# Anchor_G431.net
KiCad netlist of a schematic drawn in Altium Designer
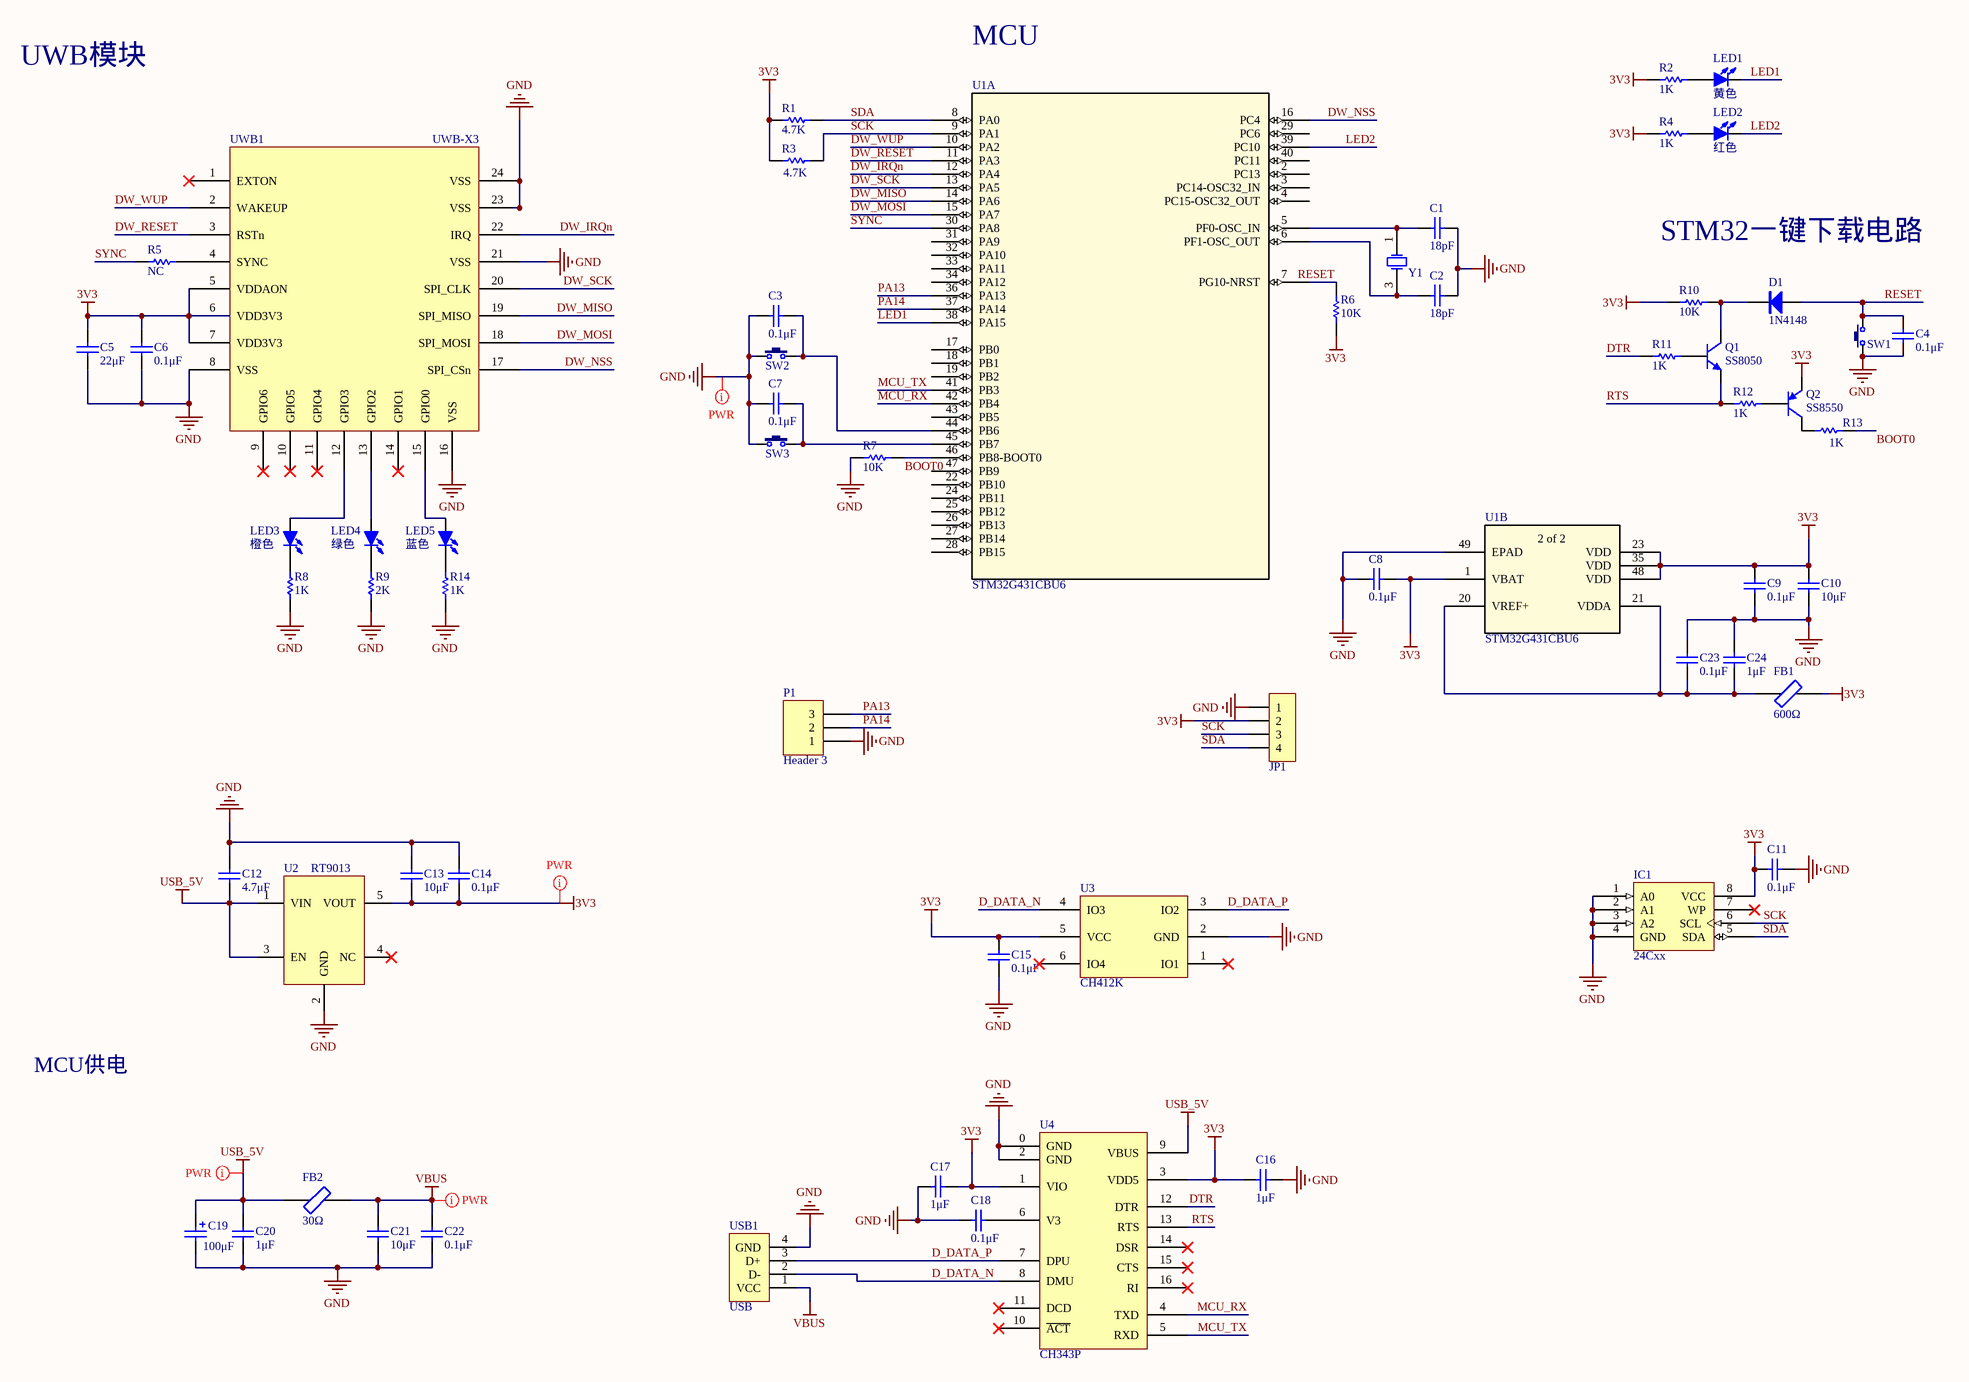
[diagram p0: Anchor_G431.SchDoc]

(export (version "E")
  (design (tool "Eeschema 10.0.6"))
  (components
    (comp (ref "C1")
      (value "18pF")
      (footprint "C 0603_L")
      (description "Capacitor")
      (fields (field (name "Comment") "Cap") (field (name "PUBLISHER") "Altium Limited"))
      (libsource (lib "Nixie") (part "Cap"))
    )
    (comp (ref "C2")
      (value "18pF")
      (footprint "C 0603_L")
      (description "Capacitor")
      (fields (field (name "Comment") "Cap") (field (name "PUBLISHER") "Altium Limited"))
      (libsource (lib "Nixie") (part "Cap"))
    )
    (comp (ref "C3")
      (value "0.1μF")
      (footprint "C 0603_L")
      (description "Capacitor")
      (fields (field (name "Comment") "Cap") (field (name "PUBLISHER") "Altium Limited"))
      (libsource (lib "Nixie") (part "Cap"))
    )
    (comp (ref "C4")
      (value "0.1μF")
      (footprint "C 0603_L")
      (description "Capacitor")
      (fields (field (name "Comment") "Cap") (field (name "PUBLISHER") "Altium Limited"))
      (libsource (lib "Nixie") (part "Cap"))
    )
    (comp (ref "C5")
      (value "22μF")
      (footprint "C 0603_L")
      (description "Capacitor")
      (fields (field (name "Comment") "Cap") (field (name "PUBLISHER") "Altium Limited"))
      (libsource (lib "Nixie") (part "Cap"))
    )
    (comp (ref "C6")
      (value "0.1μF")
      (footprint "C 0603_L")
      (description "Capacitor")
      (fields (field (name "Comment") "Cap") (field (name "PUBLISHER") "Altium Limited"))
      (libsource (lib "Nixie") (part "Cap"))
    )
    (comp (ref "C7")
      (value "0.1μF")
      (footprint "C 0603_L")
      (description "Capacitor")
      (fields (field (name "Comment") "Cap") (field (name "PUBLISHER") "Altium Limited"))
      (libsource (lib "Nixie") (part "Cap"))
    )
    (comp (ref "C8")
      (value "0.1μF")
      (footprint "C 0603_L")
      (description "Capacitor")
      (fields (field (name "Comment") "Cap") (field (name "PUBLISHER") "Altium Limited"))
      (libsource (lib "Nixie") (part "Cap"))
    )
    (comp (ref "C9")
      (value "0.1μF")
      (footprint "C 0603_L")
      (description "Capacitor")
      (fields (field (name "Comment") "Cap") (field (name "PUBLISHER") "Altium Limited"))
      (libsource (lib "Nixie") (part "Cap"))
    )
    (comp (ref "C10")
      (value "10μF")
      (footprint "C 0603_L")
      (description "Capacitor")
      (fields (field (name "Comment") "Cap") (field (name "PUBLISHER") "Altium Limited"))
      (libsource (lib "Nixie") (part "Cap"))
    )
    (comp (ref "C11")
      (value "0.1μF")
      (footprint "C 0603_L")
      (description "Capacitor")
      (fields (field (name "Comment") "Cap") (field (name "PUBLISHER") "Altium Limited"))
      (libsource (lib "Nixie") (part "Cap"))
    )
    (comp (ref "C12")
      (value "4.7μF")
      (footprint "C 0603_L")
      (description "Capacitor")
      (fields (field (name "Comment") "Cap") (field (name "PUBLISHER") "Altium Limited"))
      (libsource (lib "Nixie") (part "Cap"))
    )
    (comp (ref "C13")
      (value "10μF")
      (footprint "C 0603_L")
      (description "Capacitor")
      (fields (field (name "Comment") "Cap") (field (name "PUBLISHER") "Altium Limited"))
      (libsource (lib "Nixie") (part "Cap"))
    )
    (comp (ref "C14")
      (value "0.1μF")
      (footprint "C 0603_L")
      (description "Capacitor")
      (fields (field (name "Comment") "Cap") (field (name "PUBLISHER") "Altium Limited"))
      (libsource (lib "Nixie") (part "Cap"))
    )
    (comp (ref "C15")
      (value "0.1μF")
      (footprint "C 0603_L")
      (description "Capacitor")
      (fields (field (name "Comment") "Cap") (field (name "PUBLISHER") "Altium Limited"))
      (libsource (lib "Nixie") (part "Cap"))
    )
    (comp (ref "C16")
      (value "1μF")
      (footprint "C 0603_L")
      (description "Capacitor")
      (fields (field (name "Comment") "Cap") (field (name "PUBLISHER") "Altium Limited"))
      (libsource (lib "Nixie") (part "Cap"))
    )
    (comp (ref "C17")
      (value "1μF")
      (footprint "C 0603_L")
      (description "Capacitor")
      (fields (field (name "Comment") "Cap") (field (name "PUBLISHER") "Altium Limited"))
      (libsource (lib "Nixie") (part "Cap"))
    )
    (comp (ref "C18")
      (value "0.1μF")
      (footprint "C 0603_L")
      (description "Capacitor")
      (fields (field (name "Comment") "Cap") (field (name "PUBLISHER") "Altium Limited"))
      (libsource (lib "Nixie") (part "Cap"))
    )
    (comp (ref "C19")
      (value "100μF")
      (footprint "CM C(5*5.4)")
      (description "Polarized Capacitor (Radial)")
      (fields (field (name "Comment") "Cap Pol1") (field (name "PUBLISHER") "Altium Limited"))
      (libsource (lib "Nixie") (part "Cap Pol1"))
    )
    (comp (ref "C20")
      (value "1μF")
      (footprint "C 0603_L")
      (description "Capacitor")
      (fields (field (name "Comment") "Cap") (field (name "PUBLISHER") "Altium Limited"))
      (libsource (lib "Nixie") (part "Cap"))
    )
    (comp (ref "C21")
      (value "10μF")
      (footprint "C 0603_L")
      (description "Capacitor")
      (fields (field (name "Comment") "Cap") (field (name "PUBLISHER") "Altium Limited"))
      (libsource (lib "Nixie") (part "Cap"))
    )
    (comp (ref "C22")
      (value "0.1μF")
      (footprint "C 0603_L")
      (description "Capacitor")
      (fields (field (name "Comment") "Cap") (field (name "PUBLISHER") "Altium Limited"))
      (libsource (lib "Nixie") (part "Cap"))
    )
    (comp (ref "C23")
      (value "0.1μF")
      (footprint "C 0603_L")
      (description "Capacitor")
      (fields (field (name "Comment") "Cap") (field (name "PUBLISHER") "Altium Limited"))
      (libsource (lib "Nixie") (part "Cap"))
    )
    (comp (ref "C24")
      (value "1μF")
      (footprint "C 0603_L")
      (description "Capacitor")
      (fields (field (name "Comment") "Cap") (field (name "PUBLISHER") "Altium Limited"))
      (libsource (lib "Nixie") (part "Cap"))
    )
    (comp (ref "D1")
      (value "1N4148")
      (footprint "SOD-323")
      (description "开关二极管")
      (libsource (lib "Nixie") (part "1N4148"))
    )
    (comp (ref "FB1")
      (value "600Ω")
      (footprint "C 0603_L")
      (description "铁氧体磁珠")
      (fields (field (name "Comment") "Ferrite bead"))
      (libsource (lib "Nixie") (part "Ferrite bead"))
    )
    (comp (ref "FB2")
      (value "30Ω")
      (footprint "C 0603_L")
      (description "铁氧体磁珠")
      (fields (field (name "Comment") "Ferrite bead"))
      (libsource (lib "Nixie") (part "Ferrite bead"))
    )
    (comp (ref "IC1")
      (value "24Cxx")
      (footprint "SOP8_L")
      (description "外置EEPROM")
      (fields (field (name "版权归属") "封装库来自淘宝 ID：黄晶宝石"))
      (libsource (lib "Nixie") (part "24Cxx"))
    )
    (comp (ref "JP1")
      (value "HDR-1X4")
      (footprint "HDR2.54-LI-4P")
      (description "4P接插件")
      (fields (field (name "版权归属") "封装库来自淘宝 ID：黄晶宝石"))
      (libsource (lib "Nixie") (part "Header 4"))
    )
    (comp (ref "LED1")
      (value "黄色")
      (footprint "LED 0805G")
      (description "贴片LED")
      (fields (field (name "版权归属") "封装库来自淘宝 ID：黄晶宝石"))
      (libsource (lib "Nixie") (part "LED-SMD"))
    )
    (comp (ref "LED2")
      (value "红色")
      (footprint "LED 0805R")
      (description "贴片LED")
      (fields (field (name "版权归属") "封装库来自淘宝 ID：黄晶宝石"))
      (libsource (lib "Nixie") (part "LED-SMD"))
    )
    (comp (ref "LED3")
      (value "橙色")
      (footprint "LED 0805G")
      (description "贴片LED")
      (fields (field (name "版权归属") "封装库来自淘宝 ID：黄晶宝石"))
      (libsource (lib "Nixie") (part "LED-SMD"))
    )
    (comp (ref "LED4")
      (value "绿色")
      (footprint "LED 0805G")
      (description "贴片LED")
      (fields (field (name "版权归属") "封装库来自淘宝 ID：黄晶宝石"))
      (libsource (lib "Nixie") (part "LED-SMD"))
    )
    (comp (ref "LED5")
      (value "蓝色")
      (footprint "LED 0805G")
      (description "贴片LED")
      (fields (field (name "版权归属") "封装库来自淘宝 ID：黄晶宝石"))
      (libsource (lib "Nixie") (part "LED-SMD"))
    )
    (comp (ref "P1")
      (value "Header 3")
      (footprint "HDR2.54-LI-3P")
      (description "Header, 3-Pin")
      (fields (field (name "PUBLISHER") "Altium Limited"))
      (libsource (lib "Miscellaneous Connectors") (part "Header 3"))
    )
    (comp (ref "Q1")
      (value "SS8050")
      (footprint "SOT-23-3L")
      (description "高频放大-NPN型")
      (fields (field (name "版权归属") "封装库来自淘宝 ID：黄晶宝石"))
      (libsource (lib "Nixie") (part "8050-SMD"))
    )
    (comp (ref "Q2")
      (value "SS8550")
      (footprint "SOT-23-3L")
      (description "高频放大-PNP型")
      (fields (field (name "版权归属") "封装库来自淘宝 ID：黄晶宝石"))
      (libsource (lib "Nixie") (part "8550-SMD"))
    )
    (comp (ref "R1")
      (value "4.7K")
      (footprint "R 0603_L")
      (description "Resistor")
      (fields (field (name "PUBLISHER") "Altium Limited"))
      (libsource (lib "Nixie") (part "Resistor"))
    )
    (comp (ref "R2")
      (value "1K")
      (footprint "R 0603_L")
      (description "Resistor")
      (fields (field (name "PUBLISHER") "Altium Limited"))
      (libsource (lib "Nixie") (part "Resistor"))
    )
    (comp (ref "R3")
      (value "4.7K")
      (footprint "R 0603_L")
      (description "Resistor")
      (fields (field (name "PUBLISHER") "Altium Limited"))
      (libsource (lib "Nixie") (part "Resistor"))
    )
    (comp (ref "R4")
      (value "1K")
      (footprint "R 0603_L")
      (description "Resistor")
      (fields (field (name "PUBLISHER") "Altium Limited"))
      (libsource (lib "Nixie") (part "Resistor"))
    )
    (comp (ref "R5")
      (value "NC")
      (footprint "R 0603_L")
      (description "Resistor")
      (fields (field (name "PUBLISHER") "Altium Limited"))
      (libsource (lib "Nixie") (part "Resistor"))
    )
    (comp (ref "R6")
      (value "10K")
      (footprint "R 0603_L")
      (description "Resistor")
      (fields (field (name "PUBLISHER") "Altium Limited"))
      (libsource (lib "Nixie") (part "Resistor"))
    )
    (comp (ref "R7")
      (value "10K")
      (footprint "R 0603_L")
      (description "Resistor")
      (fields (field (name "PUBLISHER") "Altium Limited"))
      (libsource (lib "Nixie") (part "Resistor"))
    )
    (comp (ref "R8")
      (value "1K")
      (footprint "R 0603_L")
      (description "Resistor")
      (fields (field (name "PUBLISHER") "Altium Limited"))
      (libsource (lib "Nixie") (part "Resistor"))
    )
    (comp (ref "R9")
      (value "2K")
      (footprint "R 0603_L")
      (description "Resistor")
      (fields (field (name "PUBLISHER") "Altium Limited"))
      (libsource (lib "Nixie") (part "Resistor"))
    )
    (comp (ref "R10")
      (value "10K")
      (footprint "R 0603_L")
      (description "Resistor")
      (fields (field (name "PUBLISHER") "Altium Limited"))
      (libsource (lib "Nixie") (part "Resistor"))
    )
    (comp (ref "R11")
      (value "1K")
      (footprint "R 0603_L")
      (description "Resistor")
      (fields (field (name "PUBLISHER") "Altium Limited"))
      (libsource (lib "Nixie") (part "Resistor"))
    )
    (comp (ref "R12")
      (value "1K")
      (footprint "R 0603_L")
      (description "Resistor")
      (fields (field (name "PUBLISHER") "Altium Limited"))
      (libsource (lib "Nixie") (part "Resistor"))
    )
    (comp (ref "R13")
      (value "1K")
      (footprint "R 0603_L")
      (description "Resistor")
      (fields (field (name "PUBLISHER") "Altium Limited"))
      (libsource (lib "Nixie") (part "Resistor"))
    )
    (comp (ref "R14")
      (value "1K")
      (footprint "R 0603_L")
      (description "Resistor")
      (fields (field (name "PUBLISHER") "Altium Limited"))
      (libsource (lib "Nixie") (part "Resistor"))
    )
    (comp (ref "SW1")
      (value "3x6x5")
      (footprint "TSW SMD-3*6*2.5")
      (description "3x6轻触开关")
      (fields (field (name "版权归属") "封装库来自淘宝 ID：黄晶宝石"))
      (libsource (lib "") (part "TSW 3x6_1"))
    )
    (comp (ref "SW2")
      (value "3x6x5")
      (footprint "TSW SMD-3*6*2.5")
      (description "3x6轻触开关")
      (fields (field (name "版权归属") "封装库来自淘宝 ID：黄晶宝石"))
      (libsource (lib "Nixie") (part "TSW 3x6"))
    )
    (comp (ref "SW3")
      (value "3x6x5")
      (footprint "TSW SMD-3*6*2.5")
      (description "3x6轻触开关")
      (fields (field (name "版权归属") "封装库来自淘宝 ID：黄晶宝石"))
      (libsource (lib "Nixie") (part "TSW 3x6"))
    )
    (comp (ref "U1")
      (value "STM32G431CBU6")
      (footprint "UFQFPN-48_7X7X0P55MM")
      (description "No Description Available")
      (fields (field (name "COPYRIGHT") "Copyright (C) 2023 Ultra Librarian. All rights reserved."))
      (libsource (lib "Nixie") (part "STM32G431CBU6"))
    )
    (comp (ref "U2")
      (value "RT9013")
      (footprint "SOT23-5L")
      (description "LDO")
      (libsource (lib "HandHeld_terminal") (part "RT9013"))
    )
    (comp (ref "U3")
      (value "CH412K")
      (footprint "SOT-363")
      (description "四路ESD保护")
      (libsource (lib "Nixie") (part "CH412K"))
    )
    (comp (ref "U4")
      (value "CH343P")
      (footprint "QFN16")
      (description "USB转串口")
      (libsource (lib "Nixie") (part "CH343"))
    )
    (comp (ref "USB1")
      (value "USB")
      (footprint "USB_A/P_B")
      (description "USB-A型公接口")
      (fields (field (name "版权归属") "封装库来自淘宝卖家 ID：黄晶宝石"))
      (libsource (lib "Nixie") (part "USB-A/P"))
    )
    (comp (ref "UWB1")
      (value "UWB-X3")
      (footprint "UWB-X3-MAX-IPEX")
      (libsource (lib "Nixie") (part "UWB-X3(DWM3000)"))
    )
    (comp (ref "Y1")
      (value "8MHz ±20ppm 20pF")
      (footprint "OSC 3225-4P")
      (description "贴片晶振")
      (libsource (lib "HandHeld_terminal") (part "SMD-5032_2P 8MHz 20ppm 20pF"))
    )
  )
  (nets
    (net (code "1") (name "/BOOT0") (class "Default")
      (node (ref "R13") (pin "2") (pinfunction "2_2") (pintype "passive"))
      (node (ref "R7") (pin "2") (pinfunction "2_2") (pintype "passive"))
      (node (ref "U1") (pin "46") (pinfunction "PB8-BOOT0_46") (pintype "bidirectional"))
    )
    (net (code "2") (name "/DTR") (class "Default")
      (node (ref "R11") (pin "1") (pinfunction "1_1") (pintype "passive"))
      (node (ref "U4") (pin "12") (pinfunction "DTR_12") (pintype "passive"))
    )
    (net (code "3") (name "/DW_IRQn") (class "Default")
      (node (ref "U1") (pin "12") (pinfunction "PA4_12") (pintype "bidirectional"))
      (node (ref "UWB1") (pin "22") (pinfunction "IRQ_22") (pintype "passive"))
    )
    (net (code "4") (name "/DW_MISO") (class "Default")
      (node (ref "U1") (pin "14") (pinfunction "PA6_14") (pintype "bidirectional"))
      (node (ref "UWB1") (pin "19") (pinfunction "SPI_MISO_19") (pintype "passive"))
    )
    (net (code "5") (name "/DW_MOSI") (class "Default")
      (node (ref "U1") (pin "15") (pinfunction "PA7_15") (pintype "bidirectional"))
      (node (ref "UWB1") (pin "18") (pinfunction "SPI_MOSI_18") (pintype "passive"))
    )
    (net (code "6") (name "/DW_NSS") (class "Default")
      (node (ref "U1") (pin "16") (pinfunction "PC4_16") (pintype "bidirectional"))
      (node (ref "UWB1") (pin "17") (pinfunction "SPI_CSn_17") (pintype "passive"))
    )
    (net (code "7") (name "/DW_RESET") (class "Default")
      (node (ref "U1") (pin "11") (pinfunction "PA3_11") (pintype "bidirectional"))
      (node (ref "UWB1") (pin "3") (pinfunction "RSTn_3") (pintype "passive"))
    )
    (net (code "8") (name "/DW_SCK") (class "Default")
      (node (ref "U1") (pin "13") (pinfunction "PA5_13") (pintype "bidirectional"))
      (node (ref "UWB1") (pin "20") (pinfunction "SPI_CLK_20") (pintype "passive"))
    )
    (net (code "9") (name "/DW_WUP") (class "Default")
      (node (ref "U1") (pin "10") (pinfunction "PA2_10") (pintype "bidirectional"))
      (node (ref "UWB1") (pin "2") (pinfunction "WAKEUP_2") (pintype "passive"))
    )
    (net (code "10") (name "/D_DATA_N") (class "Default")
      (node (ref "U3") (pin "4") (pinfunction "IO3_4") (pintype "passive"))
      (node (ref "U4") (pin "8") (pinfunction "DMU_8") (pintype "passive"))
      (node (ref "USB1") (pin "2") (pinfunction "D-_2") (pintype "passive"))
    )
    (net (code "11") (name "/D_DATA_P") (class "Default")
      (node (ref "U3") (pin "3") (pinfunction "IO2_3") (pintype "passive"))
      (node (ref "U4") (pin "7") (pinfunction "DPU_7") (pintype "passive"))
      (node (ref "USB1") (pin "3") (pinfunction "D+_3") (pintype "passive"))
    )
    (net (code "12") (name "/LED1") (class "Default")
      (node (ref "LED1") (pin "2") (pinfunction "K_2") (pintype "passive"))
      (node (ref "U1") (pin "38") (pinfunction "PA15_38") (pintype "bidirectional"))
    )
    (net (code "13") (name "/LED2") (class "Default")
      (node (ref "LED2") (pin "2") (pinfunction "K_2") (pintype "passive"))
      (node (ref "U1") (pin "39") (pinfunction "PC10_39") (pintype "bidirectional"))
    )
    (net (code "14") (name "/MCU_RX") (class "Default")
      (node (ref "U1") (pin "42") (pinfunction "PB4_42") (pintype "bidirectional"))
      (node (ref "U4") (pin "4") (pinfunction "TXD_4") (pintype "passive"))
    )
    (net (code "15") (name "/MCU_TX") (class "Default")
      (node (ref "U1") (pin "41") (pinfunction "PB3_41") (pintype "bidirectional"))
      (node (ref "U4") (pin "5") (pinfunction "RXD_5") (pintype "passive"))
    )
    (net (code "16") (name "/PA13") (class "Default")
      (node (ref "P1") (pin "3") (pinfunction "3_3") (pintype "passive"))
      (node (ref "U1") (pin "36") (pinfunction "PA13_36") (pintype "bidirectional"))
    )
    (net (code "17") (name "/PA14") (class "Default")
      (node (ref "P1") (pin "2") (pinfunction "2_2") (pintype "passive"))
      (node (ref "U1") (pin "37") (pinfunction "PA14_37") (pintype "bidirectional"))
    )
    (net (code "18") (name "/RESET") (class "Default")
      (node (ref "C4") (pin "2") (pinfunction "2_2") (pintype "passive"))
      (node (ref "D1") (pin "1") (pinfunction "A_1") (pintype "passive"))
      (node (ref "R6") (pin "1") (pinfunction "1_1") (pintype "passive"))
      (node (ref "SW1") (pin "2") (pinfunction "2_2") (pintype "passive"))
      (node (ref "U1") (pin "7") (pinfunction "PG10-NRST_7") (pintype "bidirectional"))
    )
    (net (code "19") (name "/RTS") (class "Default")
      (node (ref "Q1") (pin "2") (pinfunction "E_2") (pintype "passive"))
      (node (ref "R12") (pin "1") (pinfunction "1_1") (pintype "passive"))
      (node (ref "U4") (pin "13") (pinfunction "RTS_13") (pintype "passive"))
    )
    (net (code "20") (name "/SCK") (class "Default")
      (node (ref "IC1") (pin "6") (pinfunction "SCL_6") (pintype "input"))
      (node (ref "JP1") (pin "3") (pinfunction "3_3") (pintype "passive"))
      (node (ref "R3") (pin "2") (pinfunction "2_2") (pintype "passive"))
      (node (ref "U1") (pin "9") (pinfunction "PA1_9") (pintype "bidirectional"))
    )
    (net (code "21") (name "/SDA") (class "Default")
      (node (ref "IC1") (pin "5") (pinfunction "SDA_5") (pintype "bidirectional"))
      (node (ref "JP1") (pin "4") (pinfunction "4_4") (pintype "passive"))
      (node (ref "R1") (pin "2") (pinfunction "2_2") (pintype "passive"))
      (node (ref "U1") (pin "8") (pinfunction "PA0_8") (pintype "bidirectional"))
    )
    (net (code "22") (name "/SYNC") (class "Default")
      (node (ref "R5") (pin "1") (pinfunction "1_1") (pintype "passive"))
      (node (ref "U1") (pin "30") (pinfunction "PA8_30") (pintype "bidirectional"))
    )
    (net (code "23") (name "3V3") (class "Default")
      (node (ref "C10") (pin "2") (pinfunction "2_2") (pintype "passive"))
      (node (ref "C11") (pin "2") (pinfunction "2_2") (pintype "passive"))
      (node (ref "C13") (pin "1") (pinfunction "1_1") (pintype "passive"))
      (node (ref "C14") (pin "1") (pinfunction "1_1") (pintype "passive"))
      (node (ref "C15") (pin "2") (pinfunction "2_2") (pintype "passive"))
      (node (ref "C16") (pin "1") (pinfunction "1_1") (pintype "passive"))
      (node (ref "C17") (pin "2") (pinfunction "2_2") (pintype "passive"))
      (node (ref "C5") (pin "2") (pinfunction "2_2") (pintype "passive"))
      (node (ref "C6") (pin "1") (pinfunction "1_1") (pintype "passive"))
      (node (ref "C8") (pin "1") (pinfunction "1_1") (pintype "passive"))
      (node (ref "C9") (pin "2") (pinfunction "2_2") (pintype "passive"))
      (node (ref "FB1") (pin "2") (pinfunction "2_2") (pintype "passive"))
      (node (ref "IC1") (pin "8") (pinfunction "VCC_8") (pintype "power_in"))
      (node (ref "JP1") (pin "2") (pinfunction "2_2") (pintype "passive"))
      (node (ref "Q2") (pin "2") (pinfunction "E_2") (pintype "passive"))
      (node (ref "R1") (pin "1") (pinfunction "1_1") (pintype "passive"))
      (node (ref "R10") (pin "1") (pinfunction "1_1") (pintype "passive"))
      (node (ref "R2") (pin "2") (pinfunction "2_2") (pintype "passive"))
      (node (ref "R3") (pin "1") (pinfunction "1_1") (pintype "passive"))
      (node (ref "R4") (pin "2") (pinfunction "2_2") (pintype "passive"))
      (node (ref "R6") (pin "2") (pinfunction "2_2") (pintype "passive"))
      (node (ref "U1") (pin "1") (pinfunction "VBAT_1") (pintype "power_in"))
      (node (ref "U1") (pin "23") (pinfunction "VDD_23") (pintype "power_in"))
      (node (ref "U1") (pin "35") (pinfunction "VDD_35") (pintype "power_in"))
      (node (ref "U1") (pin "48") (pinfunction "VDD_48") (pintype "power_in"))
      (node (ref "U2") (pin "5") (pinfunction "VOUT_5") (pintype "passive"))
      (node (ref "U3") (pin "5") (pinfunction "VCC_5") (pintype "passive"))
      (node (ref "U4") (pin "1") (pinfunction "VIO_1") (pintype "passive"))
      (node (ref "U4") (pin "3") (pinfunction "VDD5_3") (pintype "passive"))
      (node (ref "UWB1") (pin "5") (pinfunction "VDDAON_5") (pintype "passive"))
      (node (ref "UWB1") (pin "6") (pinfunction "VDD3V3_6") (pintype "passive"))
      (node (ref "UWB1") (pin "7") (pinfunction "VDD3V3_7") (pintype "passive"))
    )
    (net (code "24") (name "GND") (class "Default")
      (node (ref "C1") (pin "1") (pinfunction "1_1") (pintype "passive"))
      (node (ref "C10") (pin "1") (pinfunction "1_1") (pintype "passive"))
      (node (ref "C11") (pin "1") (pinfunction "1_1") (pintype "passive"))
      (node (ref "C12") (pin "2") (pinfunction "2_2") (pintype "passive"))
      (node (ref "C13") (pin "2") (pinfunction "2_2") (pintype "passive"))
      (node (ref "C14") (pin "2") (pinfunction "2_2") (pintype "passive"))
      (node (ref "C15") (pin "1") (pinfunction "1_1") (pintype "passive"))
      (node (ref "C16") (pin "2") (pinfunction "2_2") (pintype "passive"))
      (node (ref "C17") (pin "1") (pinfunction "1_1") (pintype "passive"))
      (node (ref "C18") (pin "1") (pinfunction "1_1") (pintype "passive"))
      (node (ref "C19") (pin "2") (pinfunction "2_2") (pintype "passive"))
      (node (ref "C2") (pin "1") (pinfunction "1_1") (pintype "passive"))
      (node (ref "C20") (pin "1") (pinfunction "1_1") (pintype "passive"))
      (node (ref "C21") (pin "1") (pinfunction "1_1") (pintype "passive"))
      (node (ref "C22") (pin "1") (pinfunction "1_1") (pintype "passive"))
      (node (ref "C23") (pin "2") (pinfunction "2_2") (pintype "passive"))
      (node (ref "C24") (pin "2") (pinfunction "2_2") (pintype "passive"))
      (node (ref "C3") (pin "2") (pinfunction "2_2") (pintype "passive"))
      (node (ref "C4") (pin "1") (pinfunction "1_1") (pintype "passive"))
      (node (ref "C5") (pin "1") (pinfunction "1_1") (pintype "passive"))
      (node (ref "C6") (pin "2") (pinfunction "2_2") (pintype "passive"))
      (node (ref "C7") (pin "2") (pinfunction "2_2") (pintype "passive"))
      (node (ref "C8") (pin "2") (pinfunction "2_2") (pintype "passive"))
      (node (ref "C9") (pin "1") (pinfunction "1_1") (pintype "passive"))
      (node (ref "IC1") (pin "1") (pinfunction "A0_1") (pintype "input"))
      (node (ref "IC1") (pin "2") (pinfunction "A1_2") (pintype "input"))
      (node (ref "IC1") (pin "3") (pinfunction "A2_3") (pintype "input"))
      (node (ref "IC1") (pin "4") (pinfunction "GND_4") (pintype "passive"))
      (node (ref "JP1") (pin "1") (pinfunction "1_1") (pintype "passive"))
      (node (ref "P1") (pin "1") (pinfunction "1_1") (pintype "passive"))
      (node (ref "R14") (pin "2") (pinfunction "2_2") (pintype "passive"))
      (node (ref "R7") (pin "1") (pinfunction "1_1") (pintype "passive"))
      (node (ref "R8") (pin "2") (pinfunction "2_2") (pintype "passive"))
      (node (ref "R9") (pin "2") (pinfunction "2_2") (pintype "passive"))
      (node (ref "SW1") (pin "1") (pinfunction "1_1") (pintype "passive"))
      (node (ref "SW2") (pin "1") (pinfunction "1_1") (pintype "passive"))
      (node (ref "SW3") (pin "1") (pinfunction "1_1") (pintype "passive"))
      (node (ref "U1") (pin "49") (pinfunction "EPAD_49") (pintype "passive"))
      (node (ref "U2") (pin "2") (pinfunction "GND_2") (pintype "passive"))
      (node (ref "U3") (pin "2") (pinfunction "GND_2") (pintype "passive"))
      (node (ref "U4") (pin "0") (pinfunction "GND_0") (pintype "passive"))
      (node (ref "U4") (pin "2") (pinfunction "GND_2") (pintype "passive"))
      (node (ref "USB1") (pin "4") (pinfunction "GND_4") (pintype "passive"))
      (node (ref "UWB1") (pin "16") (pinfunction "VSS_16") (pintype "passive"))
      (node (ref "UWB1") (pin "21") (pinfunction "VSS_21") (pintype "passive"))
      (node (ref "UWB1") (pin "23") (pinfunction "VSS_23") (pintype "passive"))
      (node (ref "UWB1") (pin "24") (pinfunction "VSS_24") (pintype "passive"))
      (node (ref "UWB1") (pin "8") (pinfunction "VSS_8") (pintype "passive"))
    )
    (net (code "25") (name "Net-(D1-K)") (class "Default")
      (node (ref "D1") (pin "2") (pinfunction "K_2") (pintype "passive"))
      (node (ref "Q1") (pin "3") (pinfunction "C_3") (pintype "passive"))
      (node (ref "R10") (pin "2") (pinfunction "2_2") (pintype "passive"))
    )
    (net (code "26") (name "Net-(LED1-A)") (class "Default")
      (node (ref "LED1") (pin "1") (pinfunction "A_1") (pintype "passive"))
      (node (ref "R2") (pin "1") (pinfunction "1_1") (pintype "passive"))
    )
    (net (code "27") (name "Net-(LED2-A)") (class "Default")
      (node (ref "LED2") (pin "1") (pinfunction "A_1") (pintype "passive"))
      (node (ref "R4") (pin "1") (pinfunction "1_1") (pintype "passive"))
    )
    (net (code "28") (name "Net-(LED3-A)") (class "Default")
      (node (ref "LED3") (pin "1") (pinfunction "A_1") (pintype "passive"))
      (node (ref "UWB1") (pin "12") (pinfunction "GPIO3_12") (pintype "passive"))
    )
    (net (code "29") (name "Net-(LED3-K)") (class "Default")
      (node (ref "LED3") (pin "2") (pinfunction "K_2") (pintype "passive"))
      (node (ref "R8") (pin "1") (pinfunction "1_1") (pintype "passive"))
    )
    (net (code "30") (name "Net-(LED4-A)") (class "Default")
      (node (ref "LED4") (pin "1") (pinfunction "A_1") (pintype "passive"))
      (node (ref "UWB1") (pin "13") (pinfunction "GPIO2_13") (pintype "passive"))
    )
    (net (code "31") (name "Net-(LED4-K)") (class "Default")
      (node (ref "LED4") (pin "2") (pinfunction "K_2") (pintype "passive"))
      (node (ref "R9") (pin "1") (pinfunction "1_1") (pintype "passive"))
    )
    (net (code "32") (name "Net-(LED5-A)") (class "Default")
      (node (ref "LED5") (pin "1") (pinfunction "A_1") (pintype "passive"))
      (node (ref "UWB1") (pin "15") (pinfunction "GPIO0_15") (pintype "passive"))
    )
    (net (code "33") (name "Net-(LED5-K)") (class "Default")
      (node (ref "LED5") (pin "2") (pinfunction "K_2") (pintype "passive"))
      (node (ref "R14") (pin "1") (pinfunction "1_1") (pintype "passive"))
    )
    (net (code "34") (name "Net-(Q1-B)") (class "Default")
      (node (ref "Q1") (pin "1") (pinfunction "B_1") (pintype "passive"))
      (node (ref "R11") (pin "2") (pinfunction "2_2") (pintype "passive"))
    )
    (net (code "35") (name "Net-(Q2-B)") (class "Default")
      (node (ref "Q2") (pin "1") (pinfunction "B_1") (pintype "passive"))
      (node (ref "R12") (pin "2") (pinfunction "2_2") (pintype "passive"))
    )
    (net (code "36") (name "Net-(Q2-C)") (class "Default")
      (node (ref "Q2") (pin "3") (pinfunction "C_3") (pintype "passive"))
      (node (ref "R13") (pin "1") (pinfunction "1_1") (pintype "passive"))
    )
    (net (code "37") (name "Net-(U1A-PB6)") (class "Default")
      (node (ref "C3") (pin "1") (pinfunction "1_1") (pintype "passive"))
      (node (ref "SW2") (pin "2") (pinfunction "2_2") (pintype "passive"))
      (node (ref "U1") (pin "44") (pinfunction "PB6_44") (pintype "bidirectional"))
    )
    (net (code "38") (name "Net-(U1A-PB7)") (class "Default")
      (node (ref "C7") (pin "1") (pinfunction "1_1") (pintype "passive"))
      (node (ref "SW3") (pin "2") (pinfunction "2_2") (pintype "passive"))
      (node (ref "U1") (pin "45") (pinfunction "PB7_45") (pintype "bidirectional"))
    )
    (net (code "39") (name "Net-(U1A-PF0-OSC_IN)") (class "Default")
      (node (ref "C1") (pin "2") (pinfunction "2_2") (pintype "passive"))
      (node (ref "U1") (pin "5") (pinfunction "PF0-OSC_IN_5") (pintype "bidirectional"))
      (node (ref "Y1") (pin "1") (pinfunction "OSC1_1") (pintype "passive"))
    )
    (net (code "40") (name "Net-(U1A-PF1-OSC_OUT)") (class "Default")
      (node (ref "C2") (pin "2") (pinfunction "2_2") (pintype "passive"))
      (node (ref "U1") (pin "6") (pinfunction "PF1-OSC_OUT_6") (pintype "bidirectional"))
      (node (ref "Y1") (pin "3") (pinfunction "OSC2_3") (pintype "passive"))
    )
    (net (code "41") (name "Net-(U1B-VDDA)") (class "Default")
      (node (ref "C23") (pin "1") (pinfunction "1_1") (pintype "passive"))
      (node (ref "C24") (pin "1") (pinfunction "1_1") (pintype "passive"))
      (node (ref "FB1") (pin "1") (pinfunction "1_1") (pintype "passive"))
      (node (ref "U1") (pin "20") (pinfunction "VREF+_20") (pintype "power_in"))
      (node (ref "U1") (pin "21") (pinfunction "VDDA_21") (pintype "power_in"))
    )
    (net (code "42") (name "Net-(U4-V3)") (class "Default")
      (node (ref "C18") (pin "2") (pinfunction "2_2") (pintype "passive"))
      (node (ref "U4") (pin "6") (pinfunction "V3_6") (pintype "passive"))
    )
    (net (code "43") (name "Net-(UWB1-SYNC)") (class "Default")
      (node (ref "R5") (pin "2") (pinfunction "2_2") (pintype "passive"))
      (node (ref "UWB1") (pin "4") (pinfunction "SYNC_4") (pintype "passive"))
    )
    (net (code "44") (name "USB_5V") (class "Default")
      (node (ref "C12") (pin "1") (pinfunction "1_1") (pintype "passive"))
      (node (ref "C19") (pin "1") (pinfunction "1_1") (pintype "passive"))
      (node (ref "C20") (pin "2") (pinfunction "2_2") (pintype "passive"))
      (node (ref "FB2") (pin "1") (pinfunction "1_1") (pintype "passive"))
      (node (ref "U2") (pin "1") (pinfunction "VIN_1") (pintype "passive"))
      (node (ref "U2") (pin "3") (pinfunction "EN_3") (pintype "passive"))
      (node (ref "U4") (pin "9") (pinfunction "VBUS_9") (pintype "passive"))
    )
    (net (code "45") (name "VBUS") (class "Default")
      (node (ref "C21") (pin "2") (pinfunction "2_2") (pintype "passive"))
      (node (ref "C22") (pin "2") (pinfunction "2_2") (pintype "passive"))
      (node (ref "FB2") (pin "2") (pinfunction "2_2") (pintype "passive"))
      (node (ref "USB1") (pin "1") (pinfunction "VCC_1") (pintype "passive"))
    )
    (net (code "46") (name "unconnected-(IC1-WP-Pad7)") (class "Default")
      (node (ref "IC1") (pin "7") (pinfunction "WP_7") (pintype "passive+no_connect"))
    )
    (net (code "47") (name "unconnected-(U1A-PA9-Pad31)") (class "Default")
      (node (ref "U1") (pin "31") (pinfunction "PA9_31") (pintype "bidirectional"))
    )
    (net (code "48") (name "unconnected-(U1A-PA10-Pad32)") (class "Default")
      (node (ref "U1") (pin "32") (pinfunction "PA10_32") (pintype "bidirectional"))
    )
    (net (code "49") (name "unconnected-(U1A-PA11-Pad33)") (class "Default")
      (node (ref "U1") (pin "33") (pinfunction "PA11_33") (pintype "bidirectional"))
    )
    (net (code "50") (name "unconnected-(U1A-PA12-Pad34)") (class "Default")
      (node (ref "U1") (pin "34") (pinfunction "PA12_34") (pintype "bidirectional"))
    )
    (net (code "51") (name "unconnected-(U1A-PB0-Pad17)") (class "Default")
      (node (ref "U1") (pin "17") (pinfunction "PB0_17") (pintype "bidirectional"))
    )
    (net (code "52") (name "unconnected-(U1A-PB1-Pad18)") (class "Default")
      (node (ref "U1") (pin "18") (pinfunction "PB1_18") (pintype "bidirectional"))
    )
    (net (code "53") (name "unconnected-(U1A-PB2-Pad19)") (class "Default")
      (node (ref "U1") (pin "19") (pinfunction "PB2_19") (pintype "bidirectional"))
    )
    (net (code "54") (name "unconnected-(U1A-PB5-Pad43)") (class "Default")
      (node (ref "U1") (pin "43") (pinfunction "PB5_43") (pintype "bidirectional"))
    )
    (net (code "55") (name "unconnected-(U1A-PB9-Pad47)") (class "Default")
      (node (ref "U1") (pin "47") (pinfunction "PB9_47") (pintype "bidirectional"))
    )
    (net (code "56") (name "unconnected-(U1A-PB10-Pad22)") (class "Default")
      (node (ref "U1") (pin "22") (pinfunction "PB10_22") (pintype "bidirectional"))
    )
    (net (code "57") (name "unconnected-(U1A-PB11-Pad24)") (class "Default")
      (node (ref "U1") (pin "24") (pinfunction "PB11_24") (pintype "bidirectional"))
    )
    (net (code "58") (name "unconnected-(U1A-PB12-Pad25)") (class "Default")
      (node (ref "U1") (pin "25") (pinfunction "PB12_25") (pintype "bidirectional"))
    )
    (net (code "59") (name "unconnected-(U1A-PB13-Pad26)") (class "Default")
      (node (ref "U1") (pin "26") (pinfunction "PB13_26") (pintype "bidirectional"))
    )
    (net (code "60") (name "unconnected-(U1A-PB14-Pad27)") (class "Default")
      (node (ref "U1") (pin "27") (pinfunction "PB14_27") (pintype "bidirectional"))
    )
    (net (code "61") (name "unconnected-(U1A-PB15-Pad28)") (class "Default")
      (node (ref "U1") (pin "28") (pinfunction "PB15_28") (pintype "bidirectional"))
    )
    (net (code "62") (name "unconnected-(U1A-PC6-Pad29)") (class "Default")
      (node (ref "U1") (pin "29") (pinfunction "PC6_29") (pintype "bidirectional"))
    )
    (net (code "63") (name "unconnected-(U1A-PC11-Pad40)") (class "Default")
      (node (ref "U1") (pin "40") (pinfunction "PC11_40") (pintype "bidirectional"))
    )
    (net (code "64") (name "unconnected-(U1A-PC13-Pad2)") (class "Default")
      (node (ref "U1") (pin "2") (pinfunction "PC13_2") (pintype "bidirectional"))
    )
    (net (code "65") (name "unconnected-(U1A-PC14-OSC32_IN-Pad3)") (class "Default")
      (node (ref "U1") (pin "3") (pinfunction "PC14-OSC32_IN_3") (pintype "bidirectional"))
    )
    (net (code "66") (name "unconnected-(U1A-PC15-OSC32_OUT-Pad4)") (class "Default")
      (node (ref "U1") (pin "4") (pinfunction "PC15-OSC32_OUT_4") (pintype "bidirectional"))
    )
    (net (code "67") (name "unconnected-(U2-NC-Pad4)") (class "Default")
      (node (ref "U2") (pin "4") (pinfunction "NC_4") (pintype "passive+no_connect"))
    )
    (net (code "68") (name "unconnected-(U3-IO1-Pad1)") (class "Default")
      (node (ref "U3") (pin "1") (pinfunction "IO1_1") (pintype "passive+no_connect"))
    )
    (net (code "69") (name "unconnected-(U3-IO4-Pad6)") (class "Default")
      (node (ref "U3") (pin "6") (pinfunction "IO4_6") (pintype "passive+no_connect"))
    )
    (net (code "70") (name "unconnected-(U4-CTS-Pad15)") (class "Default")
      (node (ref "U4") (pin "15") (pinfunction "CTS_15") (pintype "passive+no_connect"))
    )
    (net (code "71") (name "unconnected-(U4-DCD-Pad11)") (class "Default")
      (node (ref "U4") (pin "11") (pinfunction "DCD_11") (pintype "passive+no_connect"))
    )
    (net (code "72") (name "unconnected-(U4-DSR-Pad14)") (class "Default")
      (node (ref "U4") (pin "14") (pinfunction "DSR_14") (pintype "passive+no_connect"))
    )
    (net (code "73") (name "unconnected-(U4-RI-Pad16)") (class "Default")
      (node (ref "U4") (pin "16") (pinfunction "RI_16") (pintype "passive+no_connect"))
    )
    (net (code "74") (name "unconnected-(U4-~{ACT}-Pad10)") (class "Default")
      (node (ref "U4") (pin "10") (pinfunction "~{ACT}_10") (pintype "passive+no_connect"))
    )
    (net (code "75") (name "unconnected-(UWB1-EXTON-Pad1)") (class "Default")
      (node (ref "UWB1") (pin "1") (pinfunction "EXTON_1") (pintype "passive+no_connect"))
    )
    (net (code "76") (name "unconnected-(UWB1-GPIO1-Pad14)") (class "Default")
      (node (ref "UWB1") (pin "14") (pinfunction "GPIO1_14") (pintype "passive+no_connect"))
    )
    (net (code "77") (name "unconnected-(UWB1-GPIO4-Pad11)") (class "Default")
      (node (ref "UWB1") (pin "11") (pinfunction "GPIO4_11") (pintype "passive+no_connect"))
    )
    (net (code "78") (name "unconnected-(UWB1-GPIO5-Pad10)") (class "Default")
      (node (ref "UWB1") (pin "10") (pinfunction "GPIO5_10") (pintype "passive+no_connect"))
    )
    (net (code "79") (name "unconnected-(UWB1-GPIO6-Pad9)") (class "Default")
      (node (ref "UWB1") (pin "9") (pinfunction "GPIO6_9") (pintype "passive+no_connect"))
    )
  )
)
